# usb-shock-buzzer.net
KiCad netlist of a schematic drawn in EAGLE
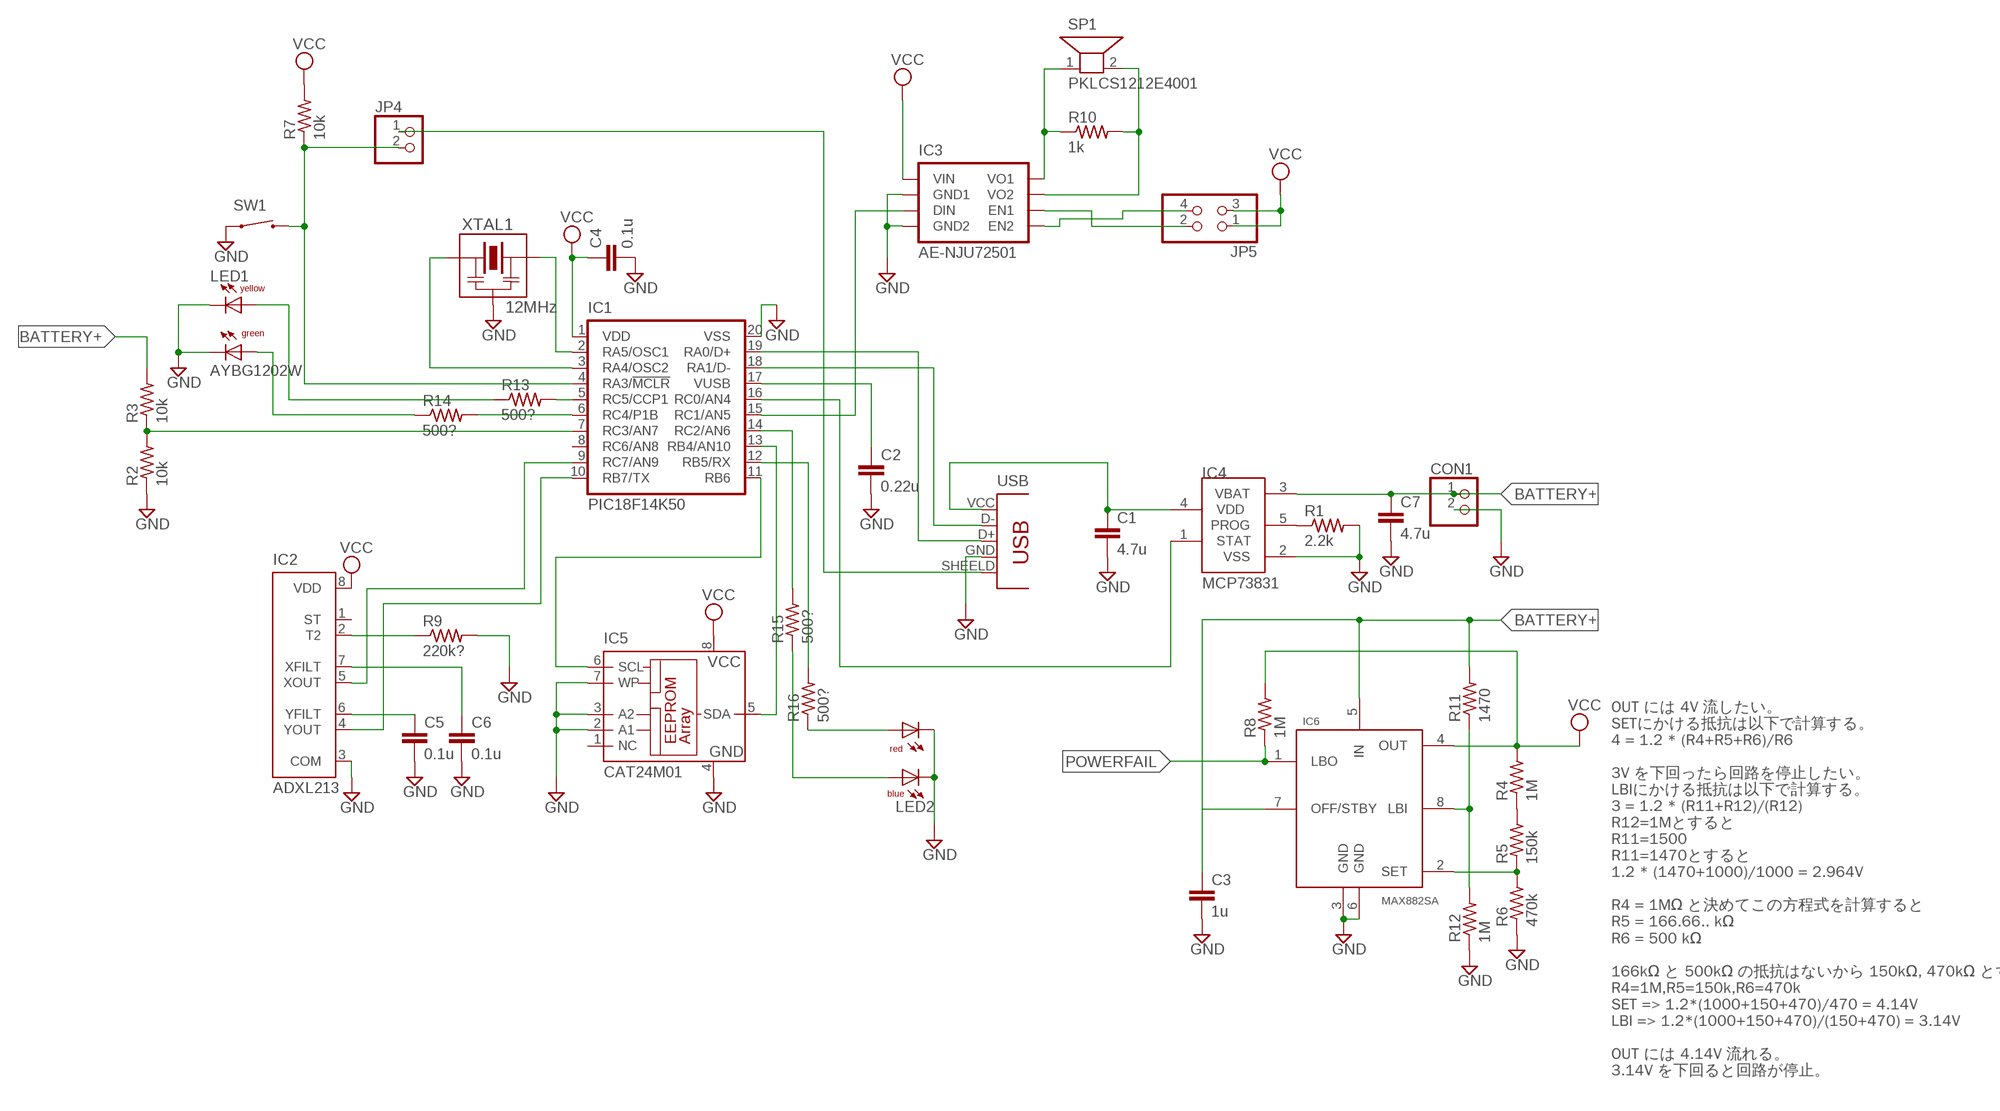
[diagram p0: schematic, sheet 1]

(export (version "E")
  (design (tool "Eeschema 10.0.6"))
  (components
    (comp (ref "C1")
      (value "4.7u")
      (footprint "eagle-import:C0805")
      (libsource (lib "eagle-import") (part "C-EUC0805"))
    )
    (comp (ref "C2")
      (value "0.22u")
      (footprint "eagle-import:C0805")
      (libsource (lib "eagle-import") (part "C-EUC0805"))
    )
    (comp (ref "C3")
      (value "1u")
      (footprint "eagle-import:C0805")
      (libsource (lib "eagle-import") (part "C-EUC0805"))
    )
    (comp (ref "C4")
      (value "0.1u")
      (footprint "eagle-import:C0805")
      (libsource (lib "eagle-import") (part "C-EUC0805"))
    )
    (comp (ref "C5")
      (value "0.1u")
      (footprint "eagle-import:C0805")
      (libsource (lib "eagle-import") (part "C-EUC0805"))
    )
    (comp (ref "C6")
      (value "0.1u")
      (footprint "eagle-import:C0805")
      (libsource (lib "eagle-import") (part "C-EUC0805"))
    )
    (comp (ref "C7")
      (value "4.7u")
      (footprint "eagle-import:C0805")
      (libsource (lib "eagle-import") (part "C-EUC0805"))
    )
    (comp (ref "CON1")
      (value "PH-2PIN")
      (footprint "eagle-import:PH-2PIN")
      (libsource (lib "eagle-import") (part "PH-2PIN"))
    )
    (comp (ref "IC1")
      (value "PIC18F14K50")
      (footprint "eagle-import:SO20")
      (libsource (lib "eagle-import") (part "PIC18F14K50"))
    )
    (comp (ref "IC2")
      (value "ADXL213")
      (footprint "eagle-import:LCC8")
      (libsource (lib "eagle-import") (part "ADXL213"))
    )
    (comp (ref "IC3")
      (value "AE-NJU72501")
      (footprint "eagle-import:AE-NJU72501")
      (libsource (lib "eagle-import") (part "AE-NJU72501"))
    )
    (comp (ref "IC4")
      (value "MCP73831")
      (footprint "eagle-import:SOT23-5L")
      (libsource (lib "eagle-import") (part "MCP73831"))
    )
    (comp (ref "IC5")
      (value "CAT24M01")
      (footprint "eagle-import:SOIC")
      (libsource (lib "eagle-import") (part "CAT24M01"))
    )
    (comp (ref "IC6")
      (value "MAX882SA")
      (footprint "eagle-import:8-SO")
      (libsource (lib "eagle-import") (part "MAX882SA"))
    )
    (comp (ref "JP4")
      (value "PINHD-1X2")
      (footprint "eagle-import:1X02")
      (libsource (lib "eagle-import") (part "PINHD-1X2"))
    )
    (comp (ref "JP5")
      (value "PINHD-2X2")
      (footprint "eagle-import:2X02")
      (libsource (lib "eagle-import") (part "PINHD-2X2"))
    )
    (comp (ref "LED1")
      (value "AYBG1202W")
      (footprint "eagle-import:AYBG1202W")
      (libsource (lib "eagle-import") (part "AYBG1202W"))
    )
    (comp (ref "LED2")
      (value "2COLOR-BR")
      (footprint "eagle-import:SML-02")
      (libsource (lib "eagle-import") (part "2COLOR-BR"))
    )
    (comp (ref "R1")
      (value "2.2k")
      (footprint "eagle-import:M0805")
      (libsource (lib "eagle-import") (part "R-US_M0805"))
    )
    (comp (ref "R2")
      (value "10k")
      (footprint "eagle-import:M0805")
      (libsource (lib "eagle-import") (part "R-US_M0805"))
    )
    (comp (ref "R3")
      (value "10k")
      (footprint "eagle-import:M0805")
      (libsource (lib "eagle-import") (part "R-US_M0805"))
    )
    (comp (ref "R4")
      (value "1M")
      (footprint "eagle-import:R0805")
      (libsource (lib "eagle-import") (part "R-US_R0805"))
    )
    (comp (ref "R5")
      (value "150k")
      (footprint "eagle-import:M0805")
      (libsource (lib "eagle-import") (part "R-US_M0805"))
    )
    (comp (ref "R6")
      (value "470k")
      (footprint "eagle-import:M0805")
      (libsource (lib "eagle-import") (part "R-US_M0805"))
    )
    (comp (ref "R7")
      (value "10k")
      (footprint "eagle-import:M0805")
      (libsource (lib "eagle-import") (part "R-US_M0805"))
    )
    (comp (ref "R8")
      (value "1M")
      (footprint "eagle-import:M0805")
      (libsource (lib "eagle-import") (part "R-US_M0805"))
    )
    (comp (ref "R9")
      (value "220k?")
      (footprint "eagle-import:M0805")
      (libsource (lib "eagle-import") (part "R-US_M0805"))
    )
    (comp (ref "R10")
      (value "1k")
      (footprint "eagle-import:M1206")
      (libsource (lib "eagle-import") (part "R-US_M1206"))
    )
    (comp (ref "R11")
      (value "1470")
      (footprint "eagle-import:R0805")
      (libsource (lib "eagle-import") (part "R-US_R0805"))
    )
    (comp (ref "R12")
      (value "1M")
      (footprint "eagle-import:R0805")
      (libsource (lib "eagle-import") (part "R-US_R0805"))
    )
    (comp (ref "R13")
      (value "500?")
      (footprint "eagle-import:M0805")
      (libsource (lib "eagle-import") (part "R-US_M0805"))
    )
    (comp (ref "R14")
      (value "500?")
      (footprint "eagle-import:M0805")
      (libsource (lib "eagle-import") (part "R-US_M0805"))
    )
    (comp (ref "R15")
      (value "500?")
      (footprint "eagle-import:M0805")
      (libsource (lib "eagle-import") (part "R-US_M0805"))
    )
    (comp (ref "R16")
      (value "500?")
      (footprint "eagle-import:M0805")
      (libsource (lib "eagle-import") (part "R-US_M0805"))
    )
    (comp (ref "SP1")
      (value "PKLCS1212E4001")
      (footprint "eagle-import:PKLCS1212E4001")
      (libsource (lib "eagle-import") (part "PKLCS1212E4001"))
    )
    (comp (ref "SW1")
      (value "TVBP06")
      (footprint "eagle-import:TVBP06")
      (libsource (lib "eagle-import") (part "TVBP06"))
    )
    (comp (ref "USB")
      (value "TYPE-A+SHILED")
      (footprint "eagle-import:TYPE-A")
      (libsource (lib "eagle-import") (part "TYPE-A+SHILED"))
    )
    (comp (ref "XTAL1")
      (value "12MHz")
      (footprint "eagle-import:CSTCE")
      (libsource (lib "eagle-import") (part "CSTCE12M0G15L"))
    )
  )
  (nets
    (net (code "1") (name "BATTERY+") (class "Default")
      (node (ref "C3") (pin "1") (pinfunction "1_1") (pintype "passive"))
      (node (ref "C7") (pin "1") (pinfunction "1_1") (pintype "passive"))
      (node (ref "CON1") (pin "1") (pinfunction "1_1") (pintype "passive"))
      (node (ref "IC4") (pin "3") (pinfunction "VBAT_3") (pintype "bidirectional"))
      (node (ref "IC6") (pin "5") (pinfunction "IN_5") (pintype "power_in"))
      (node (ref "IC6") (pin "7") (pinfunction "OFF/STBY_7") (pintype "passive"))
      (node (ref "R11") (pin "2") (pinfunction "2_2") (pintype "passive"))
      (node (ref "R3") (pin "2") (pinfunction "2_2") (pintype "passive"))
    )
    (net (code "2") (name "GND") (class "Default")
      (node (ref "C1") (pin "2") (pinfunction "2_2") (pintype "passive"))
      (node (ref "C2") (pin "2") (pinfunction "2_2") (pintype "passive"))
      (node (ref "C3") (pin "2") (pinfunction "2_2") (pintype "passive"))
      (node (ref "C4") (pin "2") (pinfunction "2_2") (pintype "passive"))
      (node (ref "C5") (pin "2") (pinfunction "2_2") (pintype "passive"))
      (node (ref "C6") (pin "2") (pinfunction "2_2") (pintype "passive"))
      (node (ref "C7") (pin "2") (pinfunction "2_2") (pintype "passive"))
      (node (ref "CON1") (pin "2") (pinfunction "2_2") (pintype "passive"))
      (node (ref "IC1") (pin "20") (pinfunction "VSS_20") (pintype "power_in"))
      (node (ref "IC2") (pin "3") (pinfunction "COM_3") (pintype "input"))
      (node (ref "IC3") (pin "2") (pinfunction "GND1_2") (pintype "power_in"))
      (node (ref "IC3") (pin "4") (pinfunction "GND2_4") (pintype "power_in"))
      (node (ref "IC4") (pin "2") (pinfunction "VSS_2") (pintype "bidirectional"))
      (node (ref "IC5") (pin "2") (pinfunction "A1_2") (pintype "input"))
      (node (ref "IC5") (pin "3") (pinfunction "A2_3") (pintype "input"))
      (node (ref "IC5") (pin "4") (pinfunction "GND_4") (pintype "power_in"))
      (node (ref "IC5") (pin "7") (pinfunction "WP_7") (pintype "input"))
      (node (ref "IC6") (pin "3") (pinfunction "GND_3") (pintype "power_in"))
      (node (ref "IC6") (pin "6") (pinfunction "GND_6") (pintype "power_in"))
      (node (ref "LED1") (pin "2") (pinfunction "CC1_2") (pintype "passive"))
      (node (ref "LED1") (pin "4") (pinfunction "CC2_4") (pintype "passive"))
      (node (ref "LED2") (pin "1") (pinfunction "CC1_1") (pintype "passive"))
      (node (ref "LED2") (pin "3") (pinfunction "CC2_3") (pintype "passive"))
      (node (ref "R1") (pin "2") (pinfunction "2_2") (pintype "passive"))
      (node (ref "R12") (pin "1") (pinfunction "1_1") (pintype "passive"))
      (node (ref "R2") (pin "1") (pinfunction "1_1") (pintype "passive"))
      (node (ref "R6") (pin "1") (pinfunction "1_1") (pintype "passive"))
      (node (ref "R9") (pin "2") (pinfunction "2_2") (pintype "passive"))
      (node (ref "SW1") (pin "1") (pinfunction "1_1") (pintype "passive"))
      (node (ref "USB") (pin "GND") (pinfunction "4_GND") (pintype "power_in"))
      (node (ref "XTAL1") (pin "2") (pinfunction "GND_2") (pintype "bidirectional"))
    )
    (net (code "3") (name "Net-(IC1-RA0{slash}D+)") (class "Default")
      (node (ref "IC1") (pin "19") (pinfunction "RA0/D+_19") (pintype "bidirectional"))
      (node (ref "USB") (pin "D+") (pinfunction "3_D+") (pintype "passive"))
    )
    (net (code "4") (name "Net-(IC1-RA1{slash}D-)") (class "Default")
      (node (ref "IC1") (pin "18") (pinfunction "RA1/D-_18") (pintype "bidirectional"))
      (node (ref "USB") (pin "D-") (pinfunction "2_D-") (pintype "passive"))
    )
    (net (code "5") (name "Net-(IC1-RA3{slash}~{MCLR})") (class "Default")
      (node (ref "IC1") (pin "4") (pinfunction "RA3/~{MCLR}_4") (pintype "bidirectional"))
      (node (ref "JP4") (pin "2") (pinfunction "2_2") (pintype "passive"))
      (node (ref "R7") (pin "1") (pinfunction "1_1") (pintype "passive"))
      (node (ref "SW1") (pin "2") (pinfunction "2_2") (pintype "passive"))
    )
    (net (code "6") (name "Net-(IC1-RA4{slash}OSC2)") (class "Default")
      (node (ref "IC1") (pin "3") (pinfunction "RA4/OSC2_3") (pintype "bidirectional"))
      (node (ref "XTAL1") (pin "1") (pinfunction "LFT_1") (pintype "bidirectional"))
    )
    (net (code "7") (name "Net-(IC1-RA5{slash}OSC1)") (class "Default")
      (node (ref "IC1") (pin "2") (pinfunction "RA5/OSC1_2") (pintype "bidirectional"))
      (node (ref "XTAL1") (pin "3") (pinfunction "RIT_3") (pintype "bidirectional"))
    )
    (net (code "8") (name "Net-(IC1-RB4{slash}AN10)") (class "Default")
      (node (ref "IC1") (pin "13") (pinfunction "RB4/AN10_13") (pintype "bidirectional"))
      (node (ref "IC5") (pin "5") (pinfunction "SDA_5") (pintype "bidirectional"))
    )
    (net (code "9") (name "Net-(IC1-RB5{slash}RX)") (class "Default")
      (node (ref "IC1") (pin "12") (pinfunction "RB5/RX_12") (pintype "bidirectional"))
      (node (ref "R16") (pin "2") (pinfunction "2_2") (pintype "passive"))
    )
    (net (code "10") (name "Net-(IC1-RB6)") (class "Default")
      (node (ref "IC1") (pin "11") (pinfunction "RB6_11") (pintype "bidirectional"))
      (node (ref "IC5") (pin "6") (pinfunction "SCL_6") (pintype "input"))
    )
    (net (code "11") (name "Net-(IC1-RB7{slash}TX)") (class "Default")
      (node (ref "IC1") (pin "10") (pinfunction "RB7/TX_10") (pintype "bidirectional"))
      (node (ref "IC2") (pin "4") (pinfunction "YOUT_4") (pintype "input"))
    )
    (net (code "12") (name "Net-(IC1-RC0{slash}AN4)") (class "Default")
      (node (ref "IC1") (pin "16") (pinfunction "RC0/AN4_16") (pintype "bidirectional"))
      (node (ref "IC4") (pin "1") (pinfunction "STAT_1") (pintype "bidirectional"))
    )
    (net (code "13") (name "Net-(IC1-RC1{slash}AN5)") (class "Default")
      (node (ref "IC1") (pin "15") (pinfunction "RC1/AN5_15") (pintype "bidirectional"))
      (node (ref "IC3") (pin "3") (pinfunction "DIN_3") (pintype "bidirectional"))
    )
    (net (code "14") (name "Net-(IC1-RC2{slash}AN6)") (class "Default")
      (node (ref "IC1") (pin "14") (pinfunction "RC2/AN6_14") (pintype "bidirectional"))
      (node (ref "R15") (pin "2") (pinfunction "2_2") (pintype "passive"))
    )
    (net (code "15") (name "Net-(IC1-RC3{slash}AN7)") (class "Default")
      (node (ref "IC1") (pin "7") (pinfunction "RC3/AN7_7") (pintype "bidirectional"))
      (node (ref "R2") (pin "2") (pinfunction "2_2") (pintype "passive"))
      (node (ref "R3") (pin "1") (pinfunction "1_1") (pintype "passive"))
    )
    (net (code "16") (name "Net-(IC1-RC4{slash}P1B)") (class "Default")
      (node (ref "IC1") (pin "6") (pinfunction "RC4/P1B_6") (pintype "bidirectional"))
      (node (ref "R14") (pin "2") (pinfunction "2_2") (pintype "passive"))
    )
    (net (code "17") (name "Net-(IC1-RC5{slash}CCP1)") (class "Default")
      (node (ref "IC1") (pin "5") (pinfunction "RC5/CCP1_5") (pintype "bidirectional"))
      (node (ref "R13") (pin "2") (pinfunction "2_2") (pintype "passive"))
    )
    (net (code "18") (name "Net-(IC1-RC7{slash}AN9)") (class "Default")
      (node (ref "IC1") (pin "9") (pinfunction "RC7/AN9_9") (pintype "bidirectional"))
      (node (ref "IC2") (pin "5") (pinfunction "XOUT_5") (pintype "input"))
    )
    (net (code "19") (name "Net-(IC1-VUSB)") (class "Default")
      (node (ref "C2") (pin "1") (pinfunction "1_1") (pintype "passive"))
      (node (ref "IC1") (pin "17") (pinfunction "VUSB_17") (pintype "bidirectional"))
    )
    (net (code "20") (name "Net-(IC2-T2)") (class "Default")
      (node (ref "IC2") (pin "2") (pinfunction "T2_2") (pintype "input"))
      (node (ref "R9") (pin "1") (pinfunction "1_1") (pintype "passive"))
    )
    (net (code "21") (name "Net-(IC2-XFILT)") (class "Default")
      (node (ref "C6") (pin "1") (pinfunction "1_1") (pintype "passive"))
      (node (ref "IC2") (pin "7") (pinfunction "XFILT_7") (pintype "input"))
    )
    (net (code "22") (name "Net-(IC2-YFILT)") (class "Default")
      (node (ref "C5") (pin "1") (pinfunction "1_1") (pintype "passive"))
      (node (ref "IC2") (pin "6") (pinfunction "YFILT_6") (pintype "input"))
    )
    (net (code "23") (name "Net-(IC3-EN1)") (class "Default")
      (node (ref "IC3") (pin "6") (pinfunction "EN1_6") (pintype "bidirectional"))
      (node (ref "JP5") (pin "2") (pinfunction "2_2") (pintype "passive"))
    )
    (net (code "24") (name "Net-(IC3-EN2)") (class "Default")
      (node (ref "IC3") (pin "5") (pinfunction "EN2_5") (pintype "power_in"))
      (node (ref "JP5") (pin "4") (pinfunction "4_4") (pintype "passive"))
    )
    (net (code "25") (name "Net-(IC3-VO1)") (class "Default")
      (node (ref "IC3") (pin "8") (pinfunction "VO1_8") (pintype "bidirectional"))
      (node (ref "R10") (pin "1") (pinfunction "1_1") (pintype "passive"))
      (node (ref "SP1") (pin "1") (pinfunction "1_1") (pintype "passive"))
    )
    (net (code "26") (name "Net-(IC3-VO2)") (class "Default")
      (node (ref "IC3") (pin "7") (pinfunction "VO2_7") (pintype "bidirectional"))
      (node (ref "R10") (pin "2") (pinfunction "2_2") (pintype "passive"))
      (node (ref "SP1") (pin "2") (pinfunction "2_2") (pintype "passive"))
    )
    (net (code "27") (name "Net-(IC4-PROG)") (class "Default")
      (node (ref "IC4") (pin "5") (pinfunction "PROG_5") (pintype "bidirectional"))
      (node (ref "R1") (pin "1") (pinfunction "1_1") (pintype "passive"))
    )
    (net (code "28") (name "Net-(IC4-VDD)") (class "Default")
      (node (ref "C1") (pin "1") (pinfunction "1_1") (pintype "passive"))
      (node (ref "IC4") (pin "4") (pinfunction "VDD_4") (pintype "bidirectional"))
      (node (ref "USB") (pin "VCC") (pinfunction "1_VCC") (pintype "power_in"))
    )
    (net (code "29") (name "Net-(IC6-LBI)") (class "Default")
      (node (ref "IC6") (pin "8") (pinfunction "LBI_8") (pintype "passive"))
      (node (ref "R11") (pin "1") (pinfunction "1_1") (pintype "passive"))
      (node (ref "R12") (pin "2") (pinfunction "2_2") (pintype "passive"))
    )
    (net (code "30") (name "Net-(IC6-SET)") (class "Default")
      (node (ref "IC6") (pin "2") (pinfunction "SET_2") (pintype "passive"))
      (node (ref "R5") (pin "1") (pinfunction "1_1") (pintype "passive"))
      (node (ref "R6") (pin "2") (pinfunction "2_2") (pintype "passive"))
    )
    (net (code "31") (name "Net-(LED1-A1)") (class "Default")
      (node (ref "LED1") (pin "1") (pinfunction "A1_1") (pintype "passive"))
      (node (ref "R13") (pin "1") (pinfunction "1_1") (pintype "passive"))
    )
    (net (code "32") (name "Net-(LED1-A2)") (class "Default")
      (node (ref "LED1") (pin "3") (pinfunction "A2_3") (pintype "passive"))
      (node (ref "R14") (pin "1") (pinfunction "1_1") (pintype "passive"))
    )
    (net (code "33") (name "Net-(LED2-AB)") (class "Default")
      (node (ref "LED2") (pin "2") (pinfunction "AB_2") (pintype "passive"))
      (node (ref "R15") (pin "1") (pinfunction "1_1") (pintype "passive"))
    )
    (net (code "34") (name "Net-(LED2-AR)") (class "Default")
      (node (ref "LED2") (pin "4") (pinfunction "AR_4") (pintype "passive"))
      (node (ref "R16") (pin "1") (pinfunction "1_1") (pintype "passive"))
    )
    (net (code "35") (name "Net-(R4-Pad1)") (class "Default")
      (node (ref "R4") (pin "1") (pinfunction "1_1") (pintype "passive"))
      (node (ref "R5") (pin "2") (pinfunction "2_2") (pintype "passive"))
    )
    (net (code "36") (name "Net-(USB-5)") (class "Default")
      (node (ref "JP4") (pin "1") (pinfunction "1_1") (pintype "passive"))
      (node (ref "USB") (pin "SHEELD") (pinfunction "5_SHEELD") (pintype "passive"))
    )
    (net (code "37") (name "POWERFAIL") (class "Default")
      (node (ref "IC6") (pin "1") (pinfunction "LBO_1") (pintype "open_collector"))
      (node (ref "R8") (pin "1") (pinfunction "1_1") (pintype "passive"))
    )
    (net (code "38") (name "VCC") (class "Default")
      (node (ref "C4") (pin "1") (pinfunction "1_1") (pintype "passive"))
      (node (ref "IC1") (pin "1") (pinfunction "VDD_1") (pintype "power_in"))
      (node (ref "IC2") (pin "8") (pinfunction "VDD_8") (pintype "input"))
      (node (ref "IC3") (pin "1") (pinfunction "VIN_1") (pintype "power_in"))
      (node (ref "IC5") (pin "8") (pinfunction "VCC_8") (pintype "power_in"))
      (node (ref "IC6") (pin "4") (pinfunction "OUT_4") (pintype "power_in"))
      (node (ref "JP5") (pin "1") (pinfunction "1_1") (pintype "passive"))
      (node (ref "JP5") (pin "3") (pinfunction "3_3") (pintype "passive"))
      (node (ref "R4") (pin "2") (pinfunction "2_2") (pintype "passive"))
      (node (ref "R7") (pin "2") (pinfunction "2_2") (pintype "passive"))
      (node (ref "R8") (pin "2") (pinfunction "2_2") (pintype "passive"))
    )
    (net (code "39") (name "unconnected-(IC1-RC6{slash}AN8-Pad8)") (class "Default")
      (node (ref "IC1") (pin "8") (pinfunction "RC6/AN8_8") (pintype "bidirectional"))
    )
    (net (code "40") (name "unconnected-(IC2-ST-Pad1)") (class "Default")
      (node (ref "IC2") (pin "1") (pinfunction "ST_1") (pintype "input"))
    )
    (net (code "41") (name "unconnected-(IC5-NC-Pad1)") (class "Default")
      (node (ref "IC5") (pin "1") (pinfunction "NC_1") (pintype "input"))
    )
  )
)
